# POVBase.net
KiCad netlist of a schematic drawn in EAGLE
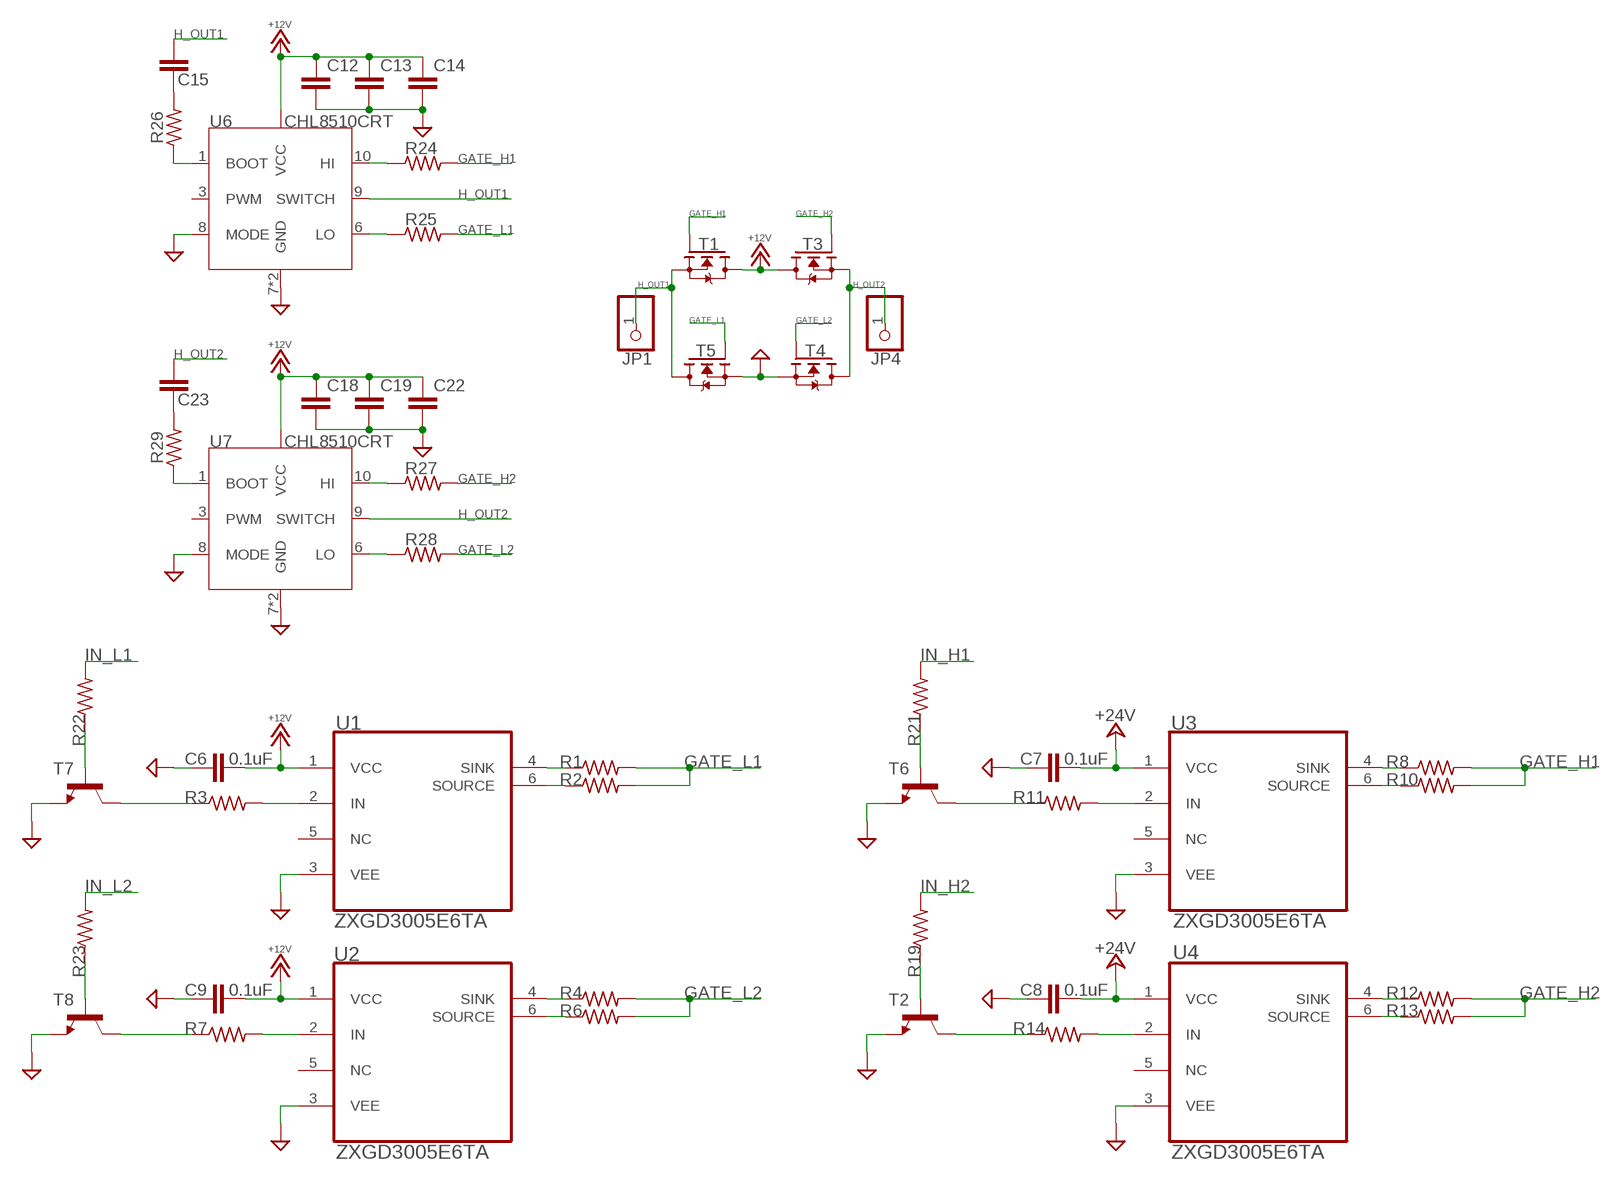
[diagram p0: schematic, sheet 1, part 1 of 2]
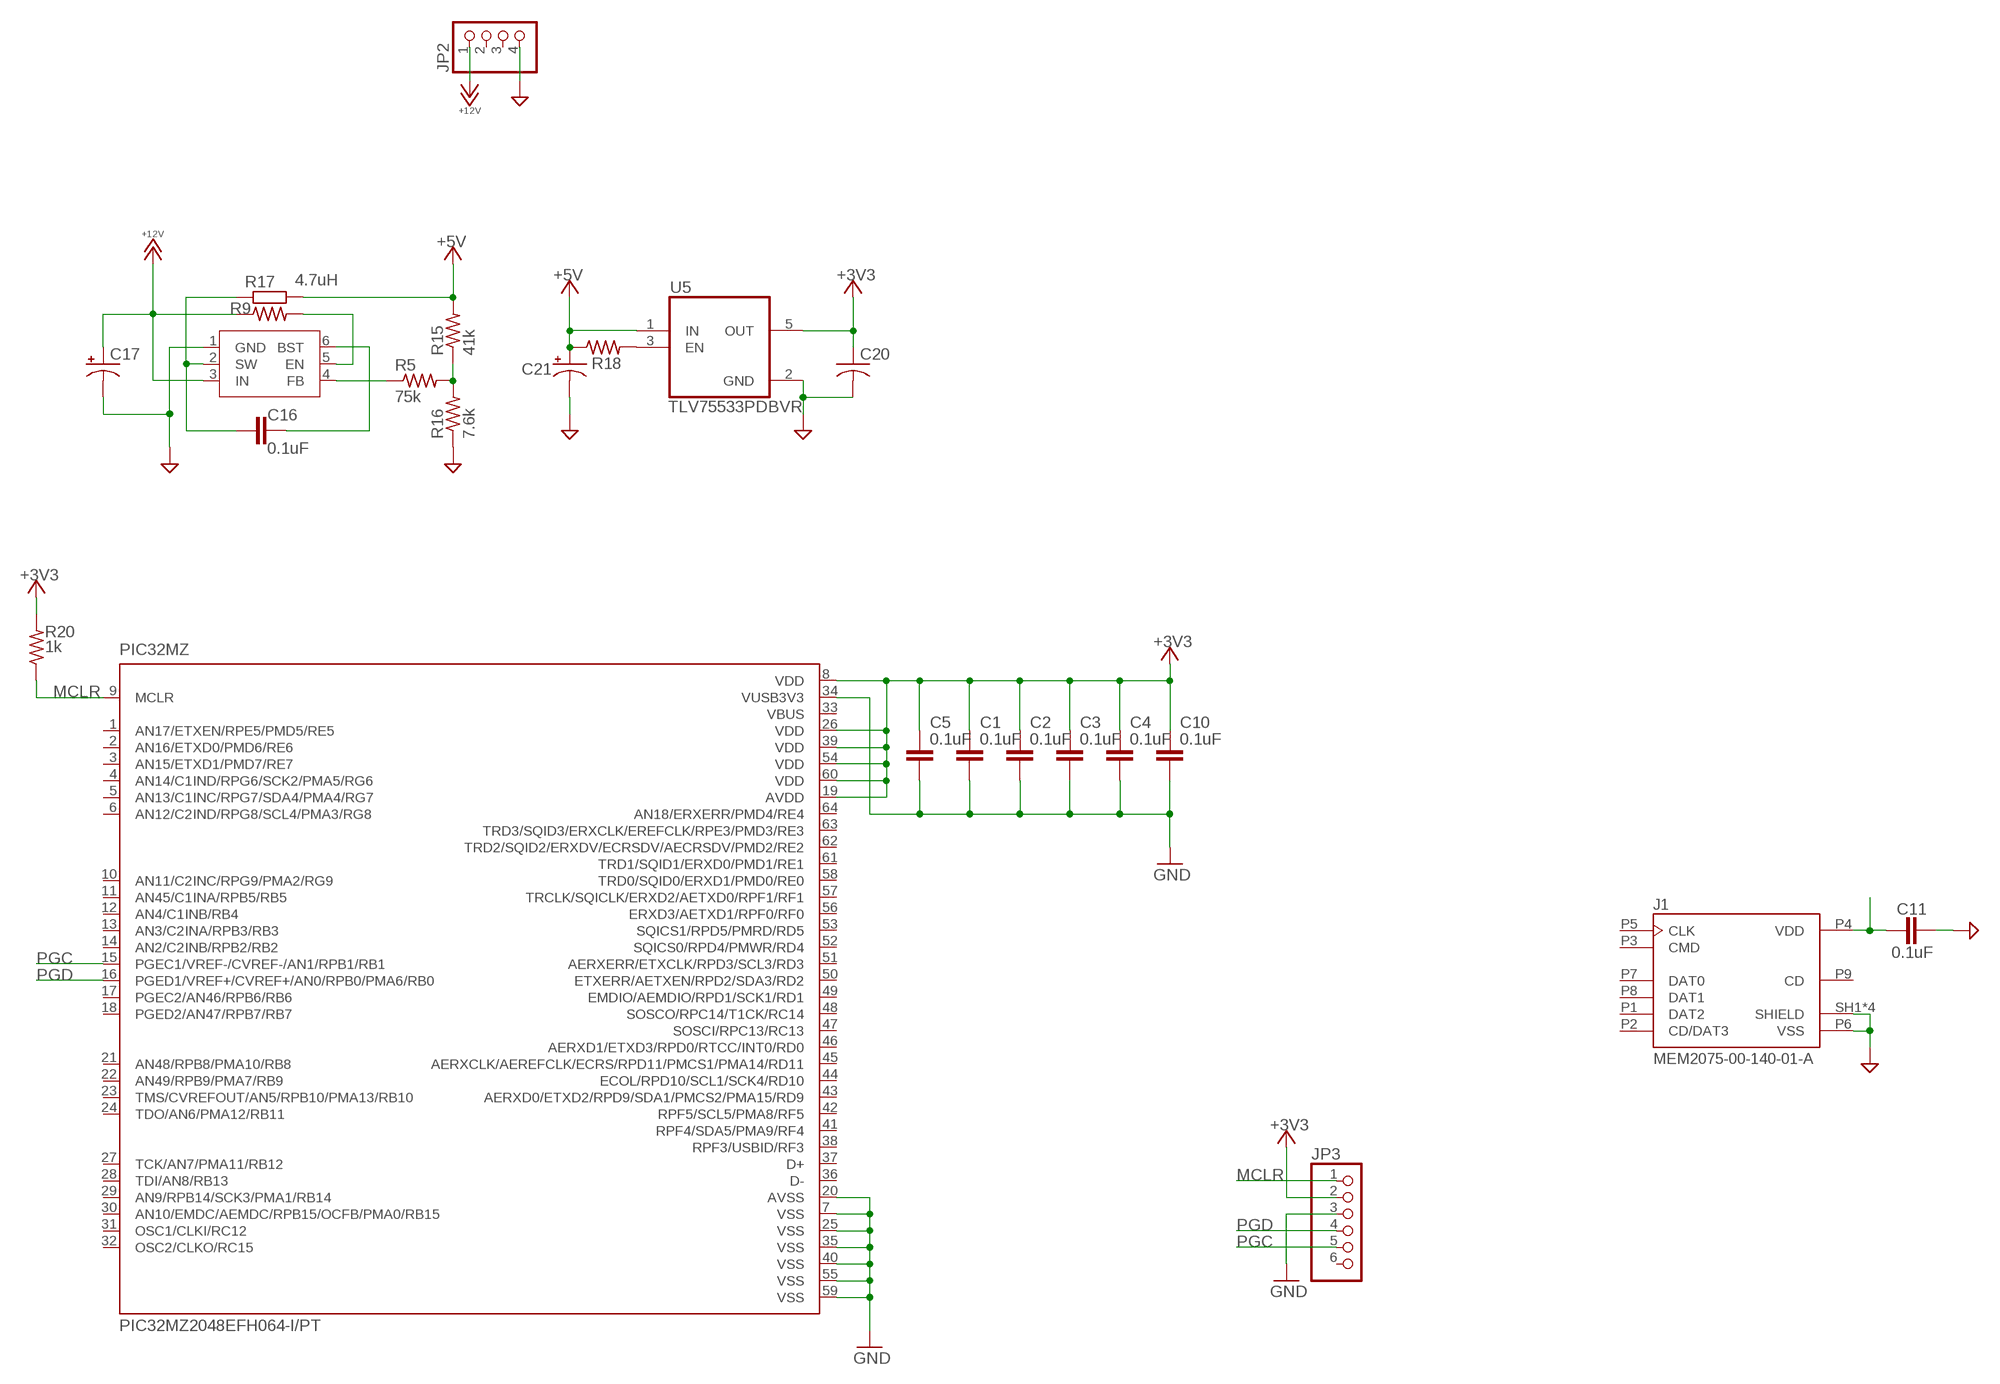
[diagram p1: schematic, sheet 1, part 2 of 2]

(export (version "E")
  (design (tool "Eeschema 10.0.6"))
  (components
    (comp (ref "C1")
      (value "0.1uF")
      (footprint "eagle-import:C0603")
      (libsource (lib "eagle-import") (part "C-EUC0603"))
    )
    (comp (ref "C2")
      (value "0.1uF")
      (footprint "eagle-import:C0603")
      (libsource (lib "eagle-import") (part "C-EUC0603"))
    )
    (comp (ref "C3")
      (value "0.1uF")
      (footprint "eagle-import:C0603")
      (libsource (lib "eagle-import") (part "C-EUC0603"))
    )
    (comp (ref "C4")
      (value "0.1uF")
      (footprint "eagle-import:C0603")
      (libsource (lib "eagle-import") (part "C-EUC0603"))
    )
    (comp (ref "C5")
      (value "0.1uF")
      (footprint "eagle-import:C0603")
      (libsource (lib "eagle-import") (part "C-EUC0603"))
    )
    (comp (ref "C6")
      (value "0.1uF")
      (footprint "eagle-import:C0805")
      (libsource (lib "eagle-import") (part "C-EUC0805"))
    )
    (comp (ref "C7")
      (value "0.1uF")
      (footprint "eagle-import:C0805")
      (libsource (lib "eagle-import") (part "C-EUC0805"))
    )
    (comp (ref "C8")
      (value "0.1uF")
      (footprint "eagle-import:C0805")
      (libsource (lib "eagle-import") (part "C-EUC0805"))
    )
    (comp (ref "C9")
      (value "0.1uF")
      (footprint "eagle-import:C0805")
      (libsource (lib "eagle-import") (part "C-EUC0805"))
    )
    (comp (ref "C10")
      (value "0.1uF")
      (footprint "eagle-import:C0603")
      (libsource (lib "eagle-import") (part "C-EUC0603"))
    )
    (comp (ref "C11")
      (value "0.1uF")
      (footprint "eagle-import:C0603")
      (libsource (lib "eagle-import") (part "C-EUC0603"))
    )
    (comp (ref "C12")
      (value "C-EUC0603")
      (footprint "eagle-import:C0603")
      (libsource (lib "eagle-import") (part "C-EUC0603"))
    )
    (comp (ref "C13")
      (value "C-EUC0603")
      (footprint "eagle-import:C0603")
      (libsource (lib "eagle-import") (part "C-EUC0603"))
    )
    (comp (ref "C14")
      (value "C-EUC0603")
      (footprint "eagle-import:C0603")
      (libsource (lib "eagle-import") (part "C-EUC0603"))
    )
    (comp (ref "C15")
      (value "C-EUC0603")
      (footprint "eagle-import:C0603")
      (libsource (lib "eagle-import") (part "C-EUC0603"))
    )
    (comp (ref "C16")
      (value "0.1uF")
      (footprint "eagle-import:C0603")
      (libsource (lib "eagle-import") (part "C-EUC0603"))
    )
    (comp (ref "C17")
      (value "CPOL-USC/6032-28R")
      (footprint "eagle-import:C_6032-28R")
      (libsource (lib "eagle-import") (part "CPOL-USC/6032-28R"))
    )
    (comp (ref "C18")
      (value "C-EUC0603")
      (footprint "eagle-import:C0603")
      (libsource (lib "eagle-import") (part "C-EUC0603"))
    )
    (comp (ref "C19")
      (value "C-EUC0603")
      (footprint "eagle-import:C0603")
      (libsource (lib "eagle-import") (part "C-EUC0603"))
    )
    (comp (ref "C20")
      (value "C-USC0805")
      (footprint "eagle-import:C0805")
      (libsource (lib "eagle-import") (part "C-USC0805"))
    )
    (comp (ref "C21")
      (value "CPOL-USB/3528-21W")
      (footprint "eagle-import:B_3528-21W")
      (libsource (lib "eagle-import") (part "CPOL-USB/3528-21W"))
    )
    (comp (ref "C22")
      (value "C-EUC0603")
      (footprint "eagle-import:C0603")
      (libsource (lib "eagle-import") (part "C-EUC0603"))
    )
    (comp (ref "C23")
      (value "C-EUC0603")
      (footprint "eagle-import:C0603")
      (libsource (lib "eagle-import") (part "C-EUC0603"))
    )
    (comp (ref "J1")
      (value "MEM2075-00-140-01-A")
      (footprint "eagle-import:GCT_MEM2075-00-140-01-A")
      (fields (field (name "MF") "Global Connector Technology"))
      (libsource (lib "eagle-import") (part "MEM2075-00-140-01-A"))
    )
    (comp (ref "JP1")
      (value "PINHD-1X1")
      (footprint "eagle-import:1X01")
      (libsource (lib "eagle-import") (part "PINHD-1X1"))
    )
    (comp (ref "JP2")
      (value "PINHD-1X4")
      (footprint "eagle-import:1X04")
      (libsource (lib "eagle-import") (part "PINHD-1X4"))
    )
    (comp (ref "JP3")
      (value "PINHD-1X6")
      (footprint "eagle-import:1X06")
      (libsource (lib "eagle-import") (part "PINHD-1X6"))
    )
    (comp (ref "JP4")
      (value "PINHD-1X1")
      (footprint "eagle-import:1X01")
      (libsource (lib "eagle-import") (part "PINHD-1X1"))
    )
    (comp (ref "PIC32MZ")
      (value "PIC32MZ2048EFH064-I/PT")
      (footprint "eagle-import:QFP50P1200X1200X120-64N")
      (fields
        (field (name "DIGI-KEY_PART_NUMBER") "PIC32MZ2048EFH064-I/PT-ND")
        (field (name "MF") "Microchip")
      )
      (libsource (lib "eagle-import") (part "PIC32MZ2048EFH064-I/PT"))
    )
    (comp (ref "R1")
      (value "R-US_R1206")
      (footprint "eagle-import:R1206")
      (libsource (lib "eagle-import") (part "R-US_R1206"))
    )
    (comp (ref "R2")
      (value "R-US_R1206")
      (footprint "eagle-import:R1206")
      (libsource (lib "eagle-import") (part "R-US_R1206"))
    )
    (comp (ref "R3")
      (value "R-US_R0603")
      (footprint "eagle-import:R0603")
      (libsource (lib "eagle-import") (part "R-US_R0603"))
    )
    (comp (ref "R4")
      (value "R-US_R1206")
      (footprint "eagle-import:R1206")
      (libsource (lib "eagle-import") (part "R-US_R1206"))
    )
    (comp (ref "R5")
      (value "75k")
      (footprint "eagle-import:R0603")
      (libsource (lib "eagle-import") (part "R-US_R0603"))
    )
    (comp (ref "R6")
      (value "R-US_R1206")
      (footprint "eagle-import:R1206")
      (libsource (lib "eagle-import") (part "R-US_R1206"))
    )
    (comp (ref "R7")
      (value "R-US_R0603")
      (footprint "eagle-import:R0603")
      (libsource (lib "eagle-import") (part "R-US_R0603"))
    )
    (comp (ref "R8")
      (value "R-US_R1206")
      (footprint "eagle-import:R1206")
      (libsource (lib "eagle-import") (part "R-US_R1206"))
    )
    (comp (ref "R9")
      (value "R-US_R0603")
      (footprint "eagle-import:R0603")
      (libsource (lib "eagle-import") (part "R-US_R0603"))
    )
    (comp (ref "R10")
      (value "R-US_R1206")
      (footprint "eagle-import:R1206")
      (libsource (lib "eagle-import") (part "R-US_R1206"))
    )
    (comp (ref "R11")
      (value "R-US_R0603")
      (footprint "eagle-import:R0603")
      (libsource (lib "eagle-import") (part "R-US_R0603"))
    )
    (comp (ref "R12")
      (value "R-US_R1206")
      (footprint "eagle-import:R1206")
      (libsource (lib "eagle-import") (part "R-US_R1206"))
    )
    (comp (ref "R13")
      (value "R-US_R1206")
      (footprint "eagle-import:R1206")
      (libsource (lib "eagle-import") (part "R-US_R1206"))
    )
    (comp (ref "R14")
      (value "R-US_R0603")
      (footprint "eagle-import:R0603")
      (libsource (lib "eagle-import") (part "R-US_R0603"))
    )
    (comp (ref "R15")
      (value "41k")
      (footprint "eagle-import:R0603")
      (libsource (lib "eagle-import") (part "R-US_R0603"))
    )
    (comp (ref "R16")
      (value "7.6k")
      (footprint "eagle-import:R0603")
      (libsource (lib "eagle-import") (part "R-US_R0603"))
    )
    (comp (ref "R17")
      (value "4.7uH")
      (footprint "eagle-import:R0805")
      (libsource (lib "eagle-import") (part "R-EU_R0805"))
    )
    (comp (ref "R18")
      (value "R-US_R0603")
      (footprint "eagle-import:R0603")
      (libsource (lib "eagle-import") (part "R-US_R0603"))
    )
    (comp (ref "R19")
      (value "R-US_R0603")
      (footprint "eagle-import:R0603")
      (libsource (lib "eagle-import") (part "R-US_R0603"))
    )
    (comp (ref "R20")
      (value "1k")
      (footprint "eagle-import:R0603")
      (libsource (lib "eagle-import") (part "R-US_R0603"))
    )
    (comp (ref "R21")
      (value "R-US_R0603")
      (footprint "eagle-import:R0603")
      (libsource (lib "eagle-import") (part "R-US_R0603"))
    )
    (comp (ref "R22")
      (value "R-US_R0603")
      (footprint "eagle-import:R0603")
      (libsource (lib "eagle-import") (part "R-US_R0603"))
    )
    (comp (ref "R23")
      (value "R-US_R0603")
      (footprint "eagle-import:R0603")
      (libsource (lib "eagle-import") (part "R-US_R0603"))
    )
    (comp (ref "R24")
      (value "R-US_R1206")
      (footprint "eagle-import:R1206")
      (libsource (lib "eagle-import") (part "R-US_R1206"))
    )
    (comp (ref "R25")
      (value "R-US_R1206")
      (footprint "eagle-import:R1206")
      (libsource (lib "eagle-import") (part "R-US_R1206"))
    )
    (comp (ref "R26")
      (value "R-US_R0603")
      (footprint "eagle-import:R0603")
      (libsource (lib "eagle-import") (part "R-US_R0603"))
    )
    (comp (ref "R27")
      (value "R-US_R1206")
      (footprint "eagle-import:R1206")
      (libsource (lib "eagle-import") (part "R-US_R1206"))
    )
    (comp (ref "R28")
      (value "R-US_R1206")
      (footprint "eagle-import:R1206")
      (libsource (lib "eagle-import") (part "R-US_R1206"))
    )
    (comp (ref "R29")
      (value "R-US_R0603")
      (footprint "eagle-import:R0603")
      (libsource (lib "eagle-import") (part "R-US_R0603"))
    )
    (comp (ref "T1")
      (value "MOSFET-N-D2PAK")
      (footprint "eagle-import:D2PAK_TO263")
      (libsource (lib "eagle-import") (part "MOSFET-N-D2PAK"))
    )
    (comp (ref "T2")
      (value "-NPN-SOT23-EBC")
      (footprint "eagle-import:SOT23-EBC")
      (libsource (lib "eagle-import") (part "-NPN-SOT23-EBC"))
    )
    (comp (ref "T3")
      (value "MOSFET-N-D2PAK")
      (footprint "eagle-import:D2PAK_TO263")
      (libsource (lib "eagle-import") (part "MOSFET-N-D2PAK"))
    )
    (comp (ref "T4")
      (value "MOSFET-N-D2PAK")
      (footprint "eagle-import:D2PAK_TO263")
      (libsource (lib "eagle-import") (part "MOSFET-N-D2PAK"))
    )
    (comp (ref "T5")
      (value "MOSFET-N-D2PAK")
      (footprint "eagle-import:D2PAK_TO263")
      (libsource (lib "eagle-import") (part "MOSFET-N-D2PAK"))
    )
    (comp (ref "T6")
      (value "-NPN-SOT23-EBC")
      (footprint "eagle-import:SOT23-EBC")
      (libsource (lib "eagle-import") (part "-NPN-SOT23-EBC"))
    )
    (comp (ref "T7")
      (value "-NPN-SOT23-EBC")
      (footprint "eagle-import:SOT23-EBC")
      (libsource (lib "eagle-import") (part "-NPN-SOT23-EBC"))
    )
    (comp (ref "T8")
      (value "-NPN-SOT23-EBC")
      (footprint "eagle-import:SOT23-EBC")
      (libsource (lib "eagle-import") (part "-NPN-SOT23-EBC"))
    )
    (comp (ref "U$2")
      (value "AP65211A")
      (footprint "eagle-import:SOT95P280X140-6N")
      (libsource (lib "eagle-import") (part "AP65211A"))
    )
    (comp (ref "U1")
      (value "ZXGD3005E6TA")
      (footprint "eagle-import:SOT95P280X130-6N")
      (fields (field (name "DIGI-KEY_PART_NUMBER") "ZXGD3005E6TADICT-ND") (field (name "MF") "Diodes Inc."))
      (libsource (lib "eagle-import") (part "ZXGD3005E6TA"))
    )
    (comp (ref "U2")
      (value "ZXGD3005E6TA")
      (footprint "eagle-import:SOT95P280X130-6N")
      (fields (field (name "DIGI-KEY_PART_NUMBER") "ZXGD3005E6TADICT-ND") (field (name "MF") "Diodes Inc."))
      (libsource (lib "eagle-import") (part "ZXGD3005E6TA"))
    )
    (comp (ref "U3")
      (value "ZXGD3005E6TA")
      (footprint "eagle-import:SOT95P280X130-6N")
      (fields (field (name "DIGI-KEY_PART_NUMBER") "ZXGD3005E6TADICT-ND") (field (name "MF") "Diodes Inc."))
      (libsource (lib "eagle-import") (part "ZXGD3005E6TA"))
    )
    (comp (ref "U4")
      (value "ZXGD3005E6TA")
      (footprint "eagle-import:SOT95P280X130-6N")
      (fields (field (name "DIGI-KEY_PART_NUMBER") "ZXGD3005E6TADICT-ND") (field (name "MF") "Diodes Inc."))
      (libsource (lib "eagle-import") (part "ZXGD3005E6TA"))
    )
    (comp (ref "U5")
      (value "TLV75533PDBVR")
      (footprint "eagle-import:SOT95P280X145-5N")
      (fields (field (name "MF") "Texas Instruments"))
      (libsource (lib "eagle-import") (part "TLV75533PDBVR"))
    )
    (comp (ref "U6")
      (value "CHL8510CRT")
      (footprint "eagle-import:10-VFDFN")
      (fields (field (name "MF") "Richtek USA") (field (name "MP") "RT6150AGQW"))
      (libsource (lib "eagle-import") (part "CHL8510CRT"))
    )
    (comp (ref "U7")
      (value "CHL8510CRT")
      (footprint "eagle-import:10-VFDFN")
      (fields (field (name "MF") "Richtek USA") (field (name "MP") "RT6150AGQW"))
      (libsource (lib "eagle-import") (part "CHL8510CRT"))
    )
  )
  (nets
    (net (code "1") (name "+3V3") (class "Default")
      (node (ref "C1") (pin "1") (pinfunction "1_1") (pintype "passive"))
      (node (ref "C10") (pin "1") (pinfunction "1_1") (pintype "passive"))
      (node (ref "C2") (pin "1") (pinfunction "1_1") (pintype "passive"))
      (node (ref "C20") (pin "1") (pinfunction "1_1") (pintype "passive"))
      (node (ref "C3") (pin "1") (pinfunction "1_1") (pintype "passive"))
      (node (ref "C4") (pin "1") (pinfunction "1_1") (pintype "passive"))
      (node (ref "C5") (pin "1") (pinfunction "1_1") (pintype "passive"))
      (node (ref "JP3") (pin "2") (pinfunction "2_2") (pintype "passive"))
      (node (ref "PIC32MZ") (pin "19") (pinfunction "AVDD_19") (pintype "power_in"))
      (node (ref "PIC32MZ") (pin "26") (pinfunction "VDD_26") (pintype "power_in"))
      (node (ref "PIC32MZ") (pin "39") (pinfunction "VDD_39") (pintype "power_in"))
      (node (ref "PIC32MZ") (pin "54") (pinfunction "VDD_54") (pintype "power_in"))
      (node (ref "PIC32MZ") (pin "60") (pinfunction "VDD_60") (pintype "power_in"))
      (node (ref "PIC32MZ") (pin "8") (pinfunction "VDD_8") (pintype "power_in"))
      (node (ref "R20") (pin "2") (pinfunction "2_2") (pintype "passive"))
      (node (ref "U5") (pin "5") (pinfunction "OUT_5") (pintype "output"))
    )
    (net (code "2") (name "+5V") (class "Default")
      (node (ref "C21") (pin "+") (pinfunction "+_+") (pintype "passive"))
      (node (ref "R15") (pin "2") (pinfunction "2_2") (pintype "passive"))
      (node (ref "R17") (pin "2") (pinfunction "2_2") (pintype "passive"))
      (node (ref "R18") (pin "1") (pinfunction "1_1") (pintype "passive"))
      (node (ref "U5") (pin "1") (pinfunction "IN_1") (pintype "input"))
    )
    (net (code "3") (name "+12V") (class "Default")
      (node (ref "C12") (pin "1") (pinfunction "1_1") (pintype "passive"))
      (node (ref "C13") (pin "1") (pinfunction "1_1") (pintype "passive"))
      (node (ref "C14") (pin "1") (pinfunction "1_1") (pintype "passive"))
      (node (ref "C17") (pin "+") (pinfunction "+_+") (pintype "passive"))
      (node (ref "C18") (pin "1") (pinfunction "1_1") (pintype "passive"))
      (node (ref "C19") (pin "1") (pinfunction "1_1") (pintype "passive"))
      (node (ref "C22") (pin "1") (pinfunction "1_1") (pintype "passive"))
      (node (ref "C6") (pin "2") (pinfunction "2_2") (pintype "passive"))
      (node (ref "C9") (pin "2") (pinfunction "2_2") (pintype "passive"))
      (node (ref "JP2") (pin "1") (pinfunction "1_1") (pintype "passive"))
      (node (ref "R9") (pin "1") (pinfunction "1_1") (pintype "passive"))
      (node (ref "T1") (pin "2") (pinfunction "D_2") (pintype "passive"))
      (node (ref "T3") (pin "2") (pinfunction "D_2") (pintype "passive"))
      (node (ref "U$2") (pin "3") (pinfunction "IN_3") (pintype "bidirectional"))
      (node (ref "U1") (pin "1") (pinfunction "VCC_1") (pintype "power_in"))
      (node (ref "U2") (pin "1") (pinfunction "VCC_1") (pintype "power_in"))
      (node (ref "U6") (pin "2") (pinfunction "VCC_2") (pintype "bidirectional"))
      (node (ref "U6") (pin "4") (pinfunction "VCC_4") (pintype "bidirectional"))
      (node (ref "U6") (pin "5") (pinfunction "VCC_5") (pintype "bidirectional"))
      (node (ref "U7") (pin "2") (pinfunction "VCC_2") (pintype "bidirectional"))
      (node (ref "U7") (pin "4") (pinfunction "VCC_4") (pintype "bidirectional"))
      (node (ref "U7") (pin "5") (pinfunction "VCC_5") (pintype "bidirectional"))
    )
    (net (code "4") (name "+24V") (class "Default")
      (node (ref "C7") (pin "2") (pinfunction "2_2") (pintype "passive"))
      (node (ref "C8") (pin "2") (pinfunction "2_2") (pintype "passive"))
      (node (ref "U3") (pin "1") (pinfunction "VCC_1") (pintype "power_in"))
      (node (ref "U4") (pin "1") (pinfunction "VCC_1") (pintype "power_in"))
    )
    (net (code "5") (name "/GATE_H1") (class "Default")
      (node (ref "R10") (pin "2") (pinfunction "2_2") (pintype "passive"))
      (node (ref "R24") (pin "2") (pinfunction "2_2") (pintype "passive"))
      (node (ref "R8") (pin "2") (pinfunction "2_2") (pintype "passive"))
      (node (ref "T1") (pin "1") (pinfunction "G_1") (pintype "passive"))
    )
    (net (code "6") (name "/GATE_H2") (class "Default")
      (node (ref "R12") (pin "2") (pinfunction "2_2") (pintype "passive"))
      (node (ref "R13") (pin "2") (pinfunction "2_2") (pintype "passive"))
      (node (ref "R27") (pin "2") (pinfunction "2_2") (pintype "passive"))
      (node (ref "T3") (pin "1") (pinfunction "G_1") (pintype "passive"))
    )
    (net (code "7") (name "/GATE_L1") (class "Default")
      (node (ref "R1") (pin "2") (pinfunction "2_2") (pintype "passive"))
      (node (ref "R2") (pin "2") (pinfunction "2_2") (pintype "passive"))
      (node (ref "R25") (pin "2") (pinfunction "2_2") (pintype "passive"))
      (node (ref "T5") (pin "1") (pinfunction "G_1") (pintype "passive"))
    )
    (net (code "8") (name "/GATE_L2") (class "Default")
      (node (ref "R28") (pin "2") (pinfunction "2_2") (pintype "passive"))
      (node (ref "R4") (pin "2") (pinfunction "2_2") (pintype "passive"))
      (node (ref "R6") (pin "2") (pinfunction "2_2") (pintype "passive"))
      (node (ref "T4") (pin "1") (pinfunction "G_1") (pintype "passive"))
    )
    (net (code "9") (name "/H_OUT1") (class "Default")
      (node (ref "C15") (pin "1") (pinfunction "1_1") (pintype "passive"))
      (node (ref "JP1") (pin "1") (pinfunction "1_1") (pintype "passive"))
      (node (ref "T1") (pin "3") (pinfunction "S_3") (pintype "passive"))
      (node (ref "T5") (pin "2") (pinfunction "D_2") (pintype "passive"))
      (node (ref "U6") (pin "9") (pinfunction "SWITCH_9") (pintype "bidirectional"))
    )
    (net (code "10") (name "/H_OUT2") (class "Default")
      (node (ref "C23") (pin "1") (pinfunction "1_1") (pintype "passive"))
      (node (ref "JP4") (pin "1") (pinfunction "1_1") (pintype "passive"))
      (node (ref "T3") (pin "3") (pinfunction "S_3") (pintype "passive"))
      (node (ref "T4") (pin "2") (pinfunction "D_2") (pintype "passive"))
      (node (ref "U7") (pin "9") (pinfunction "SWITCH_9") (pintype "bidirectional"))
    )
    (net (code "11") (name "/IN_H1") (class "Default")
      (node (ref "R21") (pin "2") (pinfunction "2_2") (pintype "passive"))
    )
    (net (code "12") (name "/IN_H2") (class "Default")
      (node (ref "R19") (pin "2") (pinfunction "2_2") (pintype "passive"))
    )
    (net (code "13") (name "/IN_L1") (class "Default")
      (node (ref "R22") (pin "2") (pinfunction "2_2") (pintype "passive"))
    )
    (net (code "14") (name "/IN_L2") (class "Default")
      (node (ref "R23") (pin "2") (pinfunction "2_2") (pintype "passive"))
    )
    (net (code "15") (name "/MCLR") (class "Default")
      (node (ref "JP3") (pin "1") (pinfunction "1_1") (pintype "passive"))
      (node (ref "PIC32MZ") (pin "9") (pinfunction "MCLR_9") (pintype "input"))
      (node (ref "R20") (pin "1") (pinfunction "1_1") (pintype "passive"))
    )
    (net (code "16") (name "/PGC") (class "Default")
      (node (ref "JP3") (pin "5") (pinfunction "5_5") (pintype "passive"))
      (node (ref "PIC32MZ") (pin "15") (pinfunction "PGEC1/VREF-/CVREF-/AN1/RPB1/RB1_15") (pintype "bidirectional"))
    )
    (net (code "17") (name "/PGD") (class "Default")
      (node (ref "JP3") (pin "4") (pinfunction "4_4") (pintype "passive"))
      (node (ref "PIC32MZ") (pin "16") (pinfunction "PGED1/VREF+/CVREF+/AN0/RPB0/PMA6/RB0_16") (pintype "bidirectional"))
    )
    (net (code "18") (name "/VBUS") (class "Default")
      (node (ref "PIC32MZ") (pin "33") (pinfunction "VBUS_33") (pintype "power_in"))
    )
    (net (code "19") (name "GND") (class "Default")
      (node (ref "C1") (pin "2") (pinfunction "2_2") (pintype "passive"))
      (node (ref "C10") (pin "2") (pinfunction "2_2") (pintype "passive"))
      (node (ref "C11") (pin "2") (pinfunction "2_2") (pintype "passive"))
      (node (ref "C12") (pin "2") (pinfunction "2_2") (pintype "passive"))
      (node (ref "C13") (pin "2") (pinfunction "2_2") (pintype "passive"))
      (node (ref "C14") (pin "2") (pinfunction "2_2") (pintype "passive"))
      (node (ref "C17") (pin "-") (pinfunction "-_-") (pintype "passive"))
      (node (ref "C18") (pin "2") (pinfunction "2_2") (pintype "passive"))
      (node (ref "C19") (pin "2") (pinfunction "2_2") (pintype "passive"))
      (node (ref "C2") (pin "2") (pinfunction "2_2") (pintype "passive"))
      (node (ref "C20") (pin "2") (pinfunction "2_2") (pintype "passive"))
      (node (ref "C21") (pin "-") (pinfunction "-_-") (pintype "passive"))
      (node (ref "C22") (pin "2") (pinfunction "2_2") (pintype "passive"))
      (node (ref "C3") (pin "2") (pinfunction "2_2") (pintype "passive"))
      (node (ref "C4") (pin "2") (pinfunction "2_2") (pintype "passive"))
      (node (ref "C5") (pin "2") (pinfunction "2_2") (pintype "passive"))
      (node (ref "C6") (pin "1") (pinfunction "1_1") (pintype "passive"))
      (node (ref "C7") (pin "1") (pinfunction "1_1") (pintype "passive"))
      (node (ref "C8") (pin "1") (pinfunction "1_1") (pintype "passive"))
      (node (ref "C9") (pin "1") (pinfunction "1_1") (pintype "passive"))
      (node (ref "J1") (pin "P6") (pinfunction "VSS_P6") (pintype "power_in"))
      (node (ref "J1") (pin "SH1") (pinfunction "SHIELD_SH1") (pintype "power_in"))
      (node (ref "J1") (pin "SH2") (pinfunction "SHIELD_SH2") (pintype "power_in"))
      (node (ref "J1") (pin "SH3") (pinfunction "SHIELD_SH3") (pintype "power_in"))
      (node (ref "J1") (pin "SH4") (pinfunction "SHIELD_SH4") (pintype "power_in"))
      (node (ref "JP2") (pin "4") (pinfunction "4_4") (pintype "passive"))
      (node (ref "JP3") (pin "3") (pinfunction "3_3") (pintype "passive"))
      (node (ref "PIC32MZ") (pin "20") (pinfunction "AVSS_20") (pintype "power_in"))
      (node (ref "PIC32MZ") (pin "25") (pinfunction "VSS_25") (pintype "power_in"))
      (node (ref "PIC32MZ") (pin "34") (pinfunction "VUSB3V3_34") (pintype "power_in"))
      (node (ref "PIC32MZ") (pin "35") (pinfunction "VSS_35") (pintype "power_in"))
      (node (ref "PIC32MZ") (pin "40") (pinfunction "VSS_40") (pintype "power_in"))
      (node (ref "PIC32MZ") (pin "55") (pinfunction "VSS_55") (pintype "power_in"))
      (node (ref "PIC32MZ") (pin "59") (pinfunction "VSS_59") (pintype "power_in"))
      (node (ref "PIC32MZ") (pin "7") (pinfunction "VSS_7") (pintype "power_in"))
      (node (ref "R16") (pin "1") (pinfunction "1_1") (pintype "passive"))
      (node (ref "T2") (pin "E") (pinfunction "E_E") (pintype "passive"))
      (node (ref "T4") (pin "3") (pinfunction "S_3") (pintype "passive"))
      (node (ref "T5") (pin "3") (pinfunction "S_3") (pintype "passive"))
      (node (ref "T6") (pin "E") (pinfunction "E_E") (pintype "passive"))
      (node (ref "T7") (pin "E") (pinfunction "E_E") (pintype "passive"))
      (node (ref "T8") (pin "E") (pinfunction "E_E") (pintype "passive"))
      (node (ref "U$2") (pin "1") (pinfunction "GND_1") (pintype "bidirectional"))
      (node (ref "U1") (pin "3") (pinfunction "VEE_3") (pintype "power_in"))
      (node (ref "U2") (pin "3") (pinfunction "VEE_3") (pintype "power_in"))
      (node (ref "U3") (pin "3") (pinfunction "VEE_3") (pintype "power_in"))
      (node (ref "U4") (pin "3") (pinfunction "VEE_3") (pintype "power_in"))
      (node (ref "U5") (pin "2") (pinfunction "GND_2") (pintype "power_in"))
      (node (ref "U6") (pin "11") (pinfunction "GND_11") (pintype "bidirectional"))
      (node (ref "U6") (pin "7") (pinfunction "GND_7") (pintype "bidirectional"))
      (node (ref "U6") (pin "8") (pinfunction "MODE_8") (pintype "bidirectional"))
      (node (ref "U7") (pin "11") (pinfunction "GND_11") (pintype "bidirectional"))
      (node (ref "U7") (pin "7") (pinfunction "GND_7") (pintype "bidirectional"))
      (node (ref "U7") (pin "8") (pinfunction "MODE_8") (pintype "bidirectional"))
    )
    (net (code "20") (name "Net-(C15-Pad2)") (class "Default")
      (node (ref "C15") (pin "2") (pinfunction "2_2") (pintype "passive"))
      (node (ref "R26") (pin "2") (pinfunction "2_2") (pintype "passive"))
    )
    (net (code "21") (name "Net-(C23-Pad2)") (class "Default")
      (node (ref "C23") (pin "2") (pinfunction "2_2") (pintype "passive"))
      (node (ref "R29") (pin "2") (pinfunction "2_2") (pintype "passive"))
    )
    (net (code "22") (name "Net-(J1-VDD)") (class "Default")
      (node (ref "C11") (pin "1") (pinfunction "1_1") (pintype "passive"))
      (node (ref "J1") (pin "P4") (pinfunction "VDD_P4") (pintype "power_in"))
    )
    (net (code "23") (name "Net-(R3-Pad1)") (class "Default")
      (node (ref "R3") (pin "1") (pinfunction "1_1") (pintype "passive"))
      (node (ref "T7") (pin "C") (pinfunction "C_C") (pintype "passive"))
    )
    (net (code "24") (name "Net-(R7-Pad1)") (class "Default")
      (node (ref "R7") (pin "1") (pinfunction "1_1") (pintype "passive"))
      (node (ref "T8") (pin "C") (pinfunction "C_C") (pintype "passive"))
    )
    (net (code "25") (name "Net-(R11-Pad1)") (class "Default")
      (node (ref "R11") (pin "1") (pinfunction "1_1") (pintype "passive"))
      (node (ref "T6") (pin "C") (pinfunction "C_C") (pintype "passive"))
    )
    (net (code "26") (name "Net-(R14-Pad1)") (class "Default")
      (node (ref "R14") (pin "1") (pinfunction "1_1") (pintype "passive"))
      (node (ref "T2") (pin "C") (pinfunction "C_C") (pintype "passive"))
    )
    (net (code "27") (name "Net-(R15-Pad1)") (class "Default")
      (node (ref "R15") (pin "1") (pinfunction "1_1") (pintype "passive"))
      (node (ref "R16") (pin "2") (pinfunction "2_2") (pintype "passive"))
      (node (ref "R5") (pin "2") (pinfunction "2_2") (pintype "passive"))
    )
    (net (code "28") (name "Net-(R19-Pad1)") (class "Default")
      (node (ref "R19") (pin "1") (pinfunction "1_1") (pintype "passive"))
      (node (ref "T2") (pin "B") (pinfunction "B_B") (pintype "passive"))
    )
    (net (code "29") (name "Net-(R21-Pad1)") (class "Default")
      (node (ref "R21") (pin "1") (pinfunction "1_1") (pintype "passive"))
      (node (ref "T6") (pin "B") (pinfunction "B_B") (pintype "passive"))
    )
    (net (code "30") (name "Net-(R22-Pad1)") (class "Default")
      (node (ref "R22") (pin "1") (pinfunction "1_1") (pintype "passive"))
      (node (ref "T7") (pin "B") (pinfunction "B_B") (pintype "passive"))
    )
    (net (code "31") (name "Net-(R23-Pad1)") (class "Default")
      (node (ref "R23") (pin "1") (pinfunction "1_1") (pintype "passive"))
      (node (ref "T8") (pin "B") (pinfunction "B_B") (pintype "passive"))
    )
    (net (code "32") (name "Net-(U$2-BST)") (class "Default")
      (node (ref "C16") (pin "2") (pinfunction "2_2") (pintype "passive"))
      (node (ref "U$2") (pin "6") (pinfunction "BST_6") (pintype "bidirectional"))
    )
    (net (code "33") (name "Net-(U$2-EN)") (class "Default")
      (node (ref "R9") (pin "2") (pinfunction "2_2") (pintype "passive"))
      (node (ref "U$2") (pin "5") (pinfunction "EN_5") (pintype "bidirectional"))
    )
    (net (code "34") (name "Net-(U$2-FB)") (class "Default")
      (node (ref "R5") (pin "1") (pinfunction "1_1") (pintype "passive"))
      (node (ref "U$2") (pin "4") (pinfunction "FB_4") (pintype "bidirectional"))
    )
    (net (code "35") (name "Net-(U$2-SW)") (class "Default")
      (node (ref "C16") (pin "1") (pinfunction "1_1") (pintype "passive"))
      (node (ref "R17") (pin "1") (pinfunction "1_1") (pintype "passive"))
      (node (ref "U$2") (pin "2") (pinfunction "SW_2") (pintype "bidirectional"))
    )
    (net (code "36") (name "Net-(U1-IN)") (class "Default")
      (node (ref "R3") (pin "2") (pinfunction "2_2") (pintype "passive"))
      (node (ref "U1") (pin "2") (pinfunction "IN_2") (pintype "input"))
    )
    (net (code "37") (name "Net-(U1-SINK)") (class "Default")
      (node (ref "R1") (pin "1") (pinfunction "1_1") (pintype "passive"))
      (node (ref "U1") (pin "4") (pinfunction "SINK_4") (pintype "output"))
    )
    (net (code "38") (name "Net-(U1-SOURCE)") (class "Default")
      (node (ref "R2") (pin "1") (pinfunction "1_1") (pintype "passive"))
      (node (ref "U1") (pin "6") (pinfunction "SOURCE_6") (pintype "output"))
    )
    (net (code "39") (name "Net-(U2-IN)") (class "Default")
      (node (ref "R7") (pin "2") (pinfunction "2_2") (pintype "passive"))
      (node (ref "U2") (pin "2") (pinfunction "IN_2") (pintype "input"))
    )
    (net (code "40") (name "Net-(U2-SINK)") (class "Default")
      (node (ref "R4") (pin "1") (pinfunction "1_1") (pintype "passive"))
      (node (ref "U2") (pin "4") (pinfunction "SINK_4") (pintype "output"))
    )
    (net (code "41") (name "Net-(U2-SOURCE)") (class "Default")
      (node (ref "R6") (pin "1") (pinfunction "1_1") (pintype "passive"))
      (node (ref "U2") (pin "6") (pinfunction "SOURCE_6") (pintype "output"))
    )
    (net (code "42") (name "Net-(U3-IN)") (class "Default")
      (node (ref "R11") (pin "2") (pinfunction "2_2") (pintype "passive"))
      (node (ref "U3") (pin "2") (pinfunction "IN_2") (pintype "input"))
    )
    (net (code "43") (name "Net-(U3-SINK)") (class "Default")
      (node (ref "R8") (pin "1") (pinfunction "1_1") (pintype "passive"))
      (node (ref "U3") (pin "4") (pinfunction "SINK_4") (pintype "output"))
    )
    (net (code "44") (name "Net-(U3-SOURCE)") (class "Default")
      (node (ref "R10") (pin "1") (pinfunction "1_1") (pintype "passive"))
      (node (ref "U3") (pin "6") (pinfunction "SOURCE_6") (pintype "output"))
    )
    (net (code "45") (name "Net-(U4-IN)") (class "Default")
      (node (ref "R14") (pin "2") (pinfunction "2_2") (pintype "passive"))
      (node (ref "U4") (pin "2") (pinfunction "IN_2") (pintype "input"))
    )
    (net (code "46") (name "Net-(U4-SINK)") (class "Default")
      (node (ref "R12") (pin "1") (pinfunction "1_1") (pintype "passive"))
      (node (ref "U4") (pin "4") (pinfunction "SINK_4") (pintype "output"))
    )
    (net (code "47") (name "Net-(U4-SOURCE)") (class "Default")
      (node (ref "R13") (pin "1") (pinfunction "1_1") (pintype "passive"))
      (node (ref "U4") (pin "6") (pinfunction "SOURCE_6") (pintype "output"))
    )
    (net (code "48") (name "Net-(U5-EN)") (class "Default")
      (node (ref "R18") (pin "2") (pinfunction "2_2") (pintype "passive"))
      (node (ref "U5") (pin "3") (pinfunction "EN_3") (pintype "input"))
    )
    (net (code "49") (name "Net-(U6-BOOT)") (class "Default")
      (node (ref "R26") (pin "1") (pinfunction "1_1") (pintype "passive"))
      (node (ref "U6") (pin "1") (pinfunction "BOOT_1") (pintype "bidirectional"))
    )
    (net (code "50") (name "Net-(U6-HI)") (class "Default")
      (node (ref "R24") (pin "1") (pinfunction "1_1") (pintype "passive"))
      (node (ref "U6") (pin "10") (pinfunction "HI_10") (pintype "bidirectional"))
    )
    (net (code "51") (name "Net-(U6-LO)") (class "Default")
      (node (ref "R25") (pin "1") (pinfunction "1_1") (pintype "passive"))
      (node (ref "U6") (pin "6") (pinfunction "LO_6") (pintype "bidirectional"))
    )
    (net (code "52") (name "Net-(U7-BOOT)") (class "Default")
      (node (ref "R29") (pin "1") (pinfunction "1_1") (pintype "passive"))
      (node (ref "U7") (pin "1") (pinfunction "BOOT_1") (pintype "bidirectional"))
    )
    (net (code "53") (name "Net-(U7-HI)") (class "Default")
      (node (ref "R27") (pin "1") (pinfunction "1_1") (pintype "passive"))
      (node (ref "U7") (pin "10") (pinfunction "HI_10") (pintype "bidirectional"))
    )
    (net (code "54") (name "Net-(U7-LO)") (class "Default")
      (node (ref "R28") (pin "1") (pinfunction "1_1") (pintype "passive"))
      (node (ref "U7") (pin "6") (pinfunction "LO_6") (pintype "bidirectional"))
    )
    (net (code "55") (name "unconnected-(J1-CD-PadP9)") (class "Default")
      (node (ref "J1") (pin "P9") (pinfunction "CD_P9") (pintype "passive"))
    )
    (net (code "56") (name "unconnected-(J1-CD{slash}DAT3-PadP2)") (class "Default")
      (node (ref "J1") (pin "P2") (pinfunction "CD/DAT3_P2") (pintype "bidirectional"))
    )
    (net (code "57") (name "unconnected-(J1-CLK-PadP5)") (class "Default")
      (node (ref "J1") (pin "P5") (pinfunction "CLK_P5") (pintype "bidirectional"))
    )
    (net (code "58") (name "unconnected-(J1-CMD-PadP3)") (class "Default")
      (node (ref "J1") (pin "P3") (pinfunction "CMD_P3") (pintype "bidirectional"))
    )
    (net (code "59") (name "unconnected-(J1-DAT0-PadP7)") (class "Default")
      (node (ref "J1") (pin "P7") (pinfunction "DAT0_P7") (pintype "bidirectional"))
    )
    (net (code "60") (name "unconnected-(J1-DAT1-PadP8)") (class "Default")
      (node (ref "J1") (pin "P8") (pinfunction "DAT1_P8") (pintype "bidirectional"))
    )
    (net (code "61") (name "unconnected-(J1-DAT2-PadP1)") (class "Default")
      (node (ref "J1") (pin "P1") (pinfunction "DAT2_P1") (pintype "bidirectional"))
    )
    (net (code "62") (name "unconnected-(JP2-Pad2)") (class "Default")
      (node (ref "JP2") (pin "2") (pinfunction "2_2") (pintype "passive"))
    )
    (net (code "63") (name "unconnected-(JP2-Pad3)") (class "Default")
      (node (ref "JP2") (pin "3") (pinfunction "3_3") (pintype "passive"))
    )
    (net (code "64") (name "unconnected-(JP3-Pad6)") (class "Default")
      (node (ref "JP3") (pin "6") (pinfunction "6_6") (pintype "passive"))
    )
    (net (code "65") (name "unconnected-(PIC32MZ-AERXCLK{slash}AEREFCLK{slash}ECRS{slash}RPD11{slash}PMCS1{slash}PMA14{slash}RD11-Pad45)") (class "Default")
      (node (ref "PIC32MZ") (pin "45") (pinfunction "AERXCLK/AEREFCLK/ECRS/RPD11/PMCS1/PMA14/RD11_45") (pintype "bidirectional"))
    )
    (net (code "66") (name "unconnected-(PIC32MZ-AERXD0{slash}ETXD2{slash}RPD9{slash}SDA1{slash}PMCS2{slash}PMA15{slash}RD9-Pad43)") (class "Default")
      (node (ref "PIC32MZ") (pin "43") (pinfunction "AERXD0/ETXD2/RPD9/SDA1/PMCS2/PMA15/RD9_43") (pintype "bidirectional"))
    )
    (net (code "67") (name "unconnected-(PIC32MZ-AERXD1{slash}ETXD3{slash}RPD0{slash}RTCC{slash}INT0{slash}RD0-Pad46)") (class "Default")
      (node (ref "PIC32MZ") (pin "46") (pinfunction "AERXD1/ETXD3/RPD0/RTCC/INT0/RD0_46") (pintype "bidirectional"))
    )
    (net (code "68") (name "unconnected-(PIC32MZ-AERXERR{slash}ETXCLK{slash}RPD3{slash}SCL3{slash}RD3-Pad51)") (class "Default")
      (node (ref "PIC32MZ") (pin "51") (pinfunction "AERXERR/ETXCLK/RPD3/SCL3/RD3_51") (pintype "bidirectional"))
    )
    (net (code "69") (name "unconnected-(PIC32MZ-AN2{slash}C2INB{slash}RPB2{slash}RB2-Pad14)") (class "Default")
      (node (ref "PIC32MZ") (pin "14") (pinfunction "AN2/C2INB/RPB2/RB2_14") (pintype "bidirectional"))
    )
    (net (code "70") (name "unconnected-(PIC32MZ-AN3{slash}C2INA{slash}RPB3{slash}RB3-Pad13)") (class "Default")
      (node (ref "PIC32MZ") (pin "13") (pinfunction "AN3/C2INA/RPB3/RB3_13") (pintype "bidirectional"))
    )
    (net (code "71") (name "unconnected-(PIC32MZ-AN4{slash}C1INB{slash}RB4-Pad12)") (class "Default")
      (node (ref "PIC32MZ") (pin "12") (pinfunction "AN4/C1INB/RB4_12") (pintype "bidirectional"))
    )
    (net (code "72") (name "unconnected-(PIC32MZ-AN9{slash}RPB14{slash}SCK3{slash}PMA1{slash}RB14-Pad29)") (class "Default")
      (node (ref "PIC32MZ") (pin "29") (pinfunction "AN9/RPB14/SCK3/PMA1/RB14_29") (pintype "bidirectional"))
    )
    (net (code "73") (name "unconnected-(PIC32MZ-AN10{slash}EMDC{slash}AEMDC{slash}RPB15{slash}OCFB{slash}PMA0{slash}RB15-Pad30)") (class "Default")
      (node (ref "PIC32MZ") (pin "30") (pinfunction "AN10/EMDC/AEMDC/RPB15/OCFB/PMA0/RB15_30") (pintype "bidirectional"))
    )
    (net (code "74") (name "unconnected-(PIC32MZ-AN11{slash}C2INC{slash}RPG9{slash}PMA2{slash}RG9-Pad10)") (class "Default")
      (node (ref "PIC32MZ") (pin "10") (pinfunction "AN11/C2INC/RPG9/PMA2/RG9_10") (pintype "bidirectional"))
    )
    (net (code "75") (name "unconnected-(PIC32MZ-AN12{slash}C2IND{slash}RPG8{slash}SCL4{slash}PMA3{slash}RG8-Pad6)") (class "Default")
      (node (ref "PIC32MZ") (pin "6") (pinfunction "AN12/C2IND/RPG8/SCL4/PMA3/RG8_6") (pintype "bidirectional"))
    )
    (net (code "76") (name "unconnected-(PIC32MZ-AN13{slash}C1INC{slash}RPG7{slash}SDA4{slash}PMA4{slash}RG7-Pad5)") (class "Default")
      (node (ref "PIC32MZ") (pin "5") (pinfunction "AN13/C1INC/RPG7/SDA4/PMA4/RG7_5") (pintype "bidirectional"))
    )
    (net (code "77") (name "unconnected-(PIC32MZ-AN14{slash}C1IND{slash}RPG6{slash}SCK2{slash}PMA5{slash}RG6-Pad4)") (class "Default")
      (node (ref "PIC32MZ") (pin "4") (pinfunction "AN14/C1IND/RPG6/SCK2/PMA5/RG6_4") (pintype "bidirectional"))
    )
    (net (code "78") (name "unconnected-(PIC32MZ-AN15{slash}ETXD1{slash}PMD7{slash}RE7-Pad3)") (class "Default")
      (node (ref "PIC32MZ") (pin "3") (pinfunction "AN15/ETXD1/PMD7/RE7_3") (pintype "bidirectional"))
    )
    (net (code "79") (name "unconnected-(PIC32MZ-AN16{slash}ETXD0{slash}PMD6{slash}RE6-Pad2)") (class "Default")
      (node (ref "PIC32MZ") (pin "2") (pinfunction "AN16/ETXD0/PMD6/RE6_2") (pintype "bidirectional"))
    )
    (net (code "80") (name "unconnected-(PIC32MZ-AN17{slash}ETXEN{slash}RPE5{slash}PMD5{slash}RE5-Pad1)") (class "Default")
      (node (ref "PIC32MZ") (pin "1") (pinfunction "AN17/ETXEN/RPE5/PMD5/RE5_1") (pintype "bidirectional"))
    )
    (net (code "81") (name "unconnected-(PIC32MZ-AN18{slash}ERXERR{slash}PMD4{slash}RE4-Pad64)") (class "Default")
      (node (ref "PIC32MZ") (pin "64") (pinfunction "AN18/ERXERR/PMD4/RE4_64") (pintype "bidirectional"))
    )
    (net (code "82") (name "unconnected-(PIC32MZ-AN45{slash}C1INA{slash}RPB5{slash}RB5-Pad11)") (class "Default")
      (node (ref "PIC32MZ") (pin "11") (pinfunction "AN45/C1INA/RPB5/RB5_11") (pintype "bidirectional"))
    )
    (net (code "83") (name "unconnected-(PIC32MZ-AN48{slash}RPB8{slash}PMA10{slash}RB8-Pad21)") (class "Default")
      (node (ref "PIC32MZ") (pin "21") (pinfunction "AN48/RPB8/PMA10/RB8_21") (pintype "bidirectional"))
    )
    (net (code "84") (name "unconnected-(PIC32MZ-AN49{slash}RPB9{slash}PMA7{slash}RB9-Pad22)") (class "Default")
      (node (ref "PIC32MZ") (pin "22") (pinfunction "AN49/RPB9/PMA7/RB9_22") (pintype "bidirectional"))
    )
    (net (code "85") (name "unconnected-(PIC32MZ-D+-Pad37)") (class "Default")
      (node (ref "PIC32MZ") (pin "37") (pinfunction "D+_37") (pintype "bidirectional"))
    )
    (net (code "86") (name "unconnected-(PIC32MZ-D--Pad36)") (class "Default")
      (node (ref "PIC32MZ") (pin "36") (pinfunction "D-_36") (pintype "bidirectional"))
    )
    (net (code "87") (name "unconnected-(PIC32MZ-ECOL{slash}RPD10{slash}SCL1{slash}SCK4{slash}RD10-Pad44)") (class "Default")
      (node (ref "PIC32MZ") (pin "44") (pinfunction "ECOL/RPD10/SCL1/SCK4/RD10_44") (pintype "bidirectional"))
    )
    (net (code "88") (name "unconnected-(PIC32MZ-EMDIO{slash}AEMDIO{slash}RPD1{slash}SCK1{slash}RD1-Pad49)") (class "Default")
      (node (ref "PIC32MZ") (pin "49") (pinfunction "EMDIO/AEMDIO/RPD1/SCK1/RD1_49") (pintype "bidirectional"))
    )
    (net (code "89") (name "unconnected-(PIC32MZ-ERXD3{slash}AETXD1{slash}RPF0{slash}RF0-Pad56)") (class "Default")
      (node (ref "PIC32MZ") (pin "56") (pinfunction "ERXD3/AETXD1/RPF0/RF0_56") (pintype "bidirectional"))
    )
    (net (code "90") (name "unconnected-(PIC32MZ-ETXERR{slash}AETXEN{slash}RPD2{slash}SDA3{slash}RD2-Pad50)") (class "Default")
      (node (ref "PIC32MZ") (pin "50") (pinfunction "ETXERR/AETXEN/RPD2/SDA3/RD2_50") (pintype "bidirectional"))
    )
    (net (code "91") (name "unconnected-(PIC32MZ-OSC1{slash}CLKI{slash}RC12-Pad31)") (class "Default")
      (node (ref "PIC32MZ") (pin "31") (pinfunction "OSC1/CLKI/RC12_31") (pintype "bidirectional"))
    )
    (net (code "92") (name "unconnected-(PIC32MZ-OSC2{slash}CLKO{slash}RC15-Pad32)") (class "Default")
      (node (ref "PIC32MZ") (pin "32") (pinfunction "OSC2/CLKO/RC15_32") (pintype "bidirectional"))
    )
    (net (code "93") (name "unconnected-(PIC32MZ-PGEC2{slash}AN46{slash}RPB6{slash}RB6-Pad17)") (class "Default")
      (node (ref "PIC32MZ") (pin "17") (pinfunction "PGEC2/AN46/RPB6/RB6_17") (pintype "bidirectional"))
    )
    (net (code "94") (name "unconnected-(PIC32MZ-PGED2{slash}AN47{slash}RPB7{slash}RB7-Pad18)") (class "Default")
      (node (ref "PIC32MZ") (pin "18") (pinfunction "PGED2/AN47/RPB7/RB7_18") (pintype "bidirectional"))
    )
    (net (code "95") (name "unconnected-(PIC32MZ-RPF3{slash}USBID{slash}RF3-Pad38)") (class "Default")
      (node (ref "PIC32MZ") (pin "38") (pinfunction "RPF3/USBID/RF3_38") (pintype "bidirectional"))
    )
    (net (code "96") (name "unconnected-(PIC32MZ-RPF4{slash}SDA5{slash}PMA9{slash}RF4-Pad41)") (class "Default")
      (node (ref "PIC32MZ") (pin "41") (pinfunction "RPF4/SDA5/PMA9/RF4_41") (pintype "bidirectional"))
    )
    (net (code "97") (name "unconnected-(PIC32MZ-RPF5{slash}SCL5{slash}PMA8{slash}RF5-Pad42)") (class "Default")
      (node (ref "PIC32MZ") (pin "42") (pinfunction "RPF5/SCL5/PMA8/RF5_42") (pintype "bidirectional"))
    )
    (net (code "98") (name "unconnected-(PIC32MZ-SOSCI{slash}RPC13{slash}RC13-Pad47)") (class "Default")
      (node (ref "PIC32MZ") (pin "47") (pinfunction "SOSCI/RPC13/RC13_47") (pintype "bidirectional"))
    )
    (net (code "99") (name "unconnected-(PIC32MZ-SOSCO{slash}RPC14{slash}T1CK{slash}RC14-Pad48)") (class "Default")
      (node (ref "PIC32MZ") (pin "48") (pinfunction "SOSCO/RPC14/T1CK/RC14_48") (pintype "bidirectional"))
    )
    (net (code "100") (name "unconnected-(PIC32MZ-SQICS0{slash}RPD4{slash}PMWR{slash}RD4-Pad52)") (class "Default")
      (node (ref "PIC32MZ") (pin "52") (pinfunction "SQICS0/RPD4/PMWR/RD4_52") (pintype "bidirectional"))
    )
    (net (code "101") (name "unconnected-(PIC32MZ-SQICS1{slash}RPD5{slash}PMRD{slash}RD5-Pad53)") (class "Default")
      (node (ref "PIC32MZ") (pin "53") (pinfunction "SQICS1/RPD5/PMRD/RD5_53") (pintype "bidirectional"))
    )
    (net (code "102") (name "unconnected-(PIC32MZ-TCK{slash}AN7{slash}PMA11{slash}RB12-Pad27)") (class "Default")
      (node (ref "PIC32MZ") (pin "27") (pinfunction "TCK/AN7/PMA11/RB12_27") (pintype "bidirectional"))
    )
    (net (code "103") (name "unconnected-(PIC32MZ-TDI{slash}AN8{slash}RB13-Pad28)") (class "Default")
      (node (ref "PIC32MZ") (pin "28") (pinfunction "TDI/AN8/RB13_28") (pintype "bidirectional"))
    )
    (net (code "104") (name "unconnected-(PIC32MZ-TDO{slash}AN6{slash}PMA12{slash}RB11-Pad24)") (class "Default")
      (node (ref "PIC32MZ") (pin "24") (pinfunction "TDO/AN6/PMA12/RB11_24") (pintype "bidirectional"))
    )
    (net (code "105") (name "unconnected-(PIC32MZ-TMS{slash}CVREFOUT{slash}AN5{slash}RPB10{slash}PMA13{slash}RB10-Pad23)") (class "Default")
      (node (ref "PIC32MZ") (pin "23") (pinfunction "TMS/CVREFOUT/AN5/RPB10/PMA13/RB10_23") (pintype "bidirectional"))
    )
    (net (code "106") (name "unconnected-(PIC32MZ-TRCLK{slash}SQICLK{slash}ERXD2{slash}AETXD0{slash}RPF1{slash}RF1-Pad57)") (class "Default")
      (node (ref "PIC32MZ") (pin "57") (pinfunction "TRCLK/SQICLK/ERXD2/AETXD0/RPF1/RF1_57") (pintype "bidirectional"))
    )
    (net (code "107") (name "unconnected-(PIC32MZ-TRD0{slash}SQID0{slash}ERXD1{slash}PMD0{slash}RE0-Pad58)") (class "Default")
      (node (ref "PIC32MZ") (pin "58") (pinfunction "TRD0/SQID0/ERXD1/PMD0/RE0_58") (pintype "bidirectional"))
    )
    (net (code "108") (name "unconnected-(PIC32MZ-TRD1{slash}SQID1{slash}ERXD0{slash}PMD1{slash}RE1-Pad61)") (class "Default")
      (node (ref "PIC32MZ") (pin "61") (pinfunction "TRD1/SQID1/ERXD0/PMD1/RE1_61") (pintype "bidirectional"))
    )
    (net (code "109") (name "unconnected-(PIC32MZ-TRD2{slash}SQID2{slash}ERXDV{slash}ECRSDV{slash}AECRSDV{slash}PMD2{slash}RE2-Pad62)") (class "Default")
      (node (ref "PIC32MZ") (pin "62") (pinfunction "TRD2/SQID2/ERXDV/ECRSDV/AECRSDV/PMD2/RE2_62") (pintype "bidirectional"))
    )
    (net (code "110") (name "unconnected-(PIC32MZ-TRD3{slash}SQID3{slash}ERXCLK{slash}EREFCLK{slash}RPE3{slash}PMD3{slash}RE3-Pad63)") (class "Default")
      (node (ref "PIC32MZ") (pin "63") (pinfunction "TRD3/SQID3/ERXCLK/EREFCLK/RPE3/PMD3/RE3_63") (pintype "bidirectional"))
    )
    (net (code "111") (name "unconnected-(U1-NC-Pad5)") (class "Default")
      (node (ref "U1") (pin "5") (pinfunction "NC_5") (pintype "no_connect"))
    )
    (net (code "112") (name "unconnected-(U2-NC-Pad5)") (class "Default")
      (node (ref "U2") (pin "5") (pinfunction "NC_5") (pintype "no_connect"))
    )
    (net (code "113") (name "unconnected-(U3-NC-Pad5)") (class "Default")
      (node (ref "U3") (pin "5") (pinfunction "NC_5") (pintype "no_connect"))
    )
    (net (code "114") (name "unconnected-(U4-NC-Pad5)") (class "Default")
      (node (ref "U4") (pin "5") (pinfunction "NC_5") (pintype "no_connect"))
    )
    (net (code "115") (name "unconnected-(U6-PWM-Pad3)") (class "Default")
      (node (ref "U6") (pin "3") (pinfunction "PWM_3") (pintype "bidirectional"))
    )
    (net (code "116") (name "unconnected-(U7-PWM-Pad3)") (class "Default")
      (node (ref "U7") (pin "3") (pinfunction "PWM_3") (pintype "bidirectional"))
    )
  )
)
